# Sheet1.net
KiCad netlist of a schematic drawn in Altium Designer
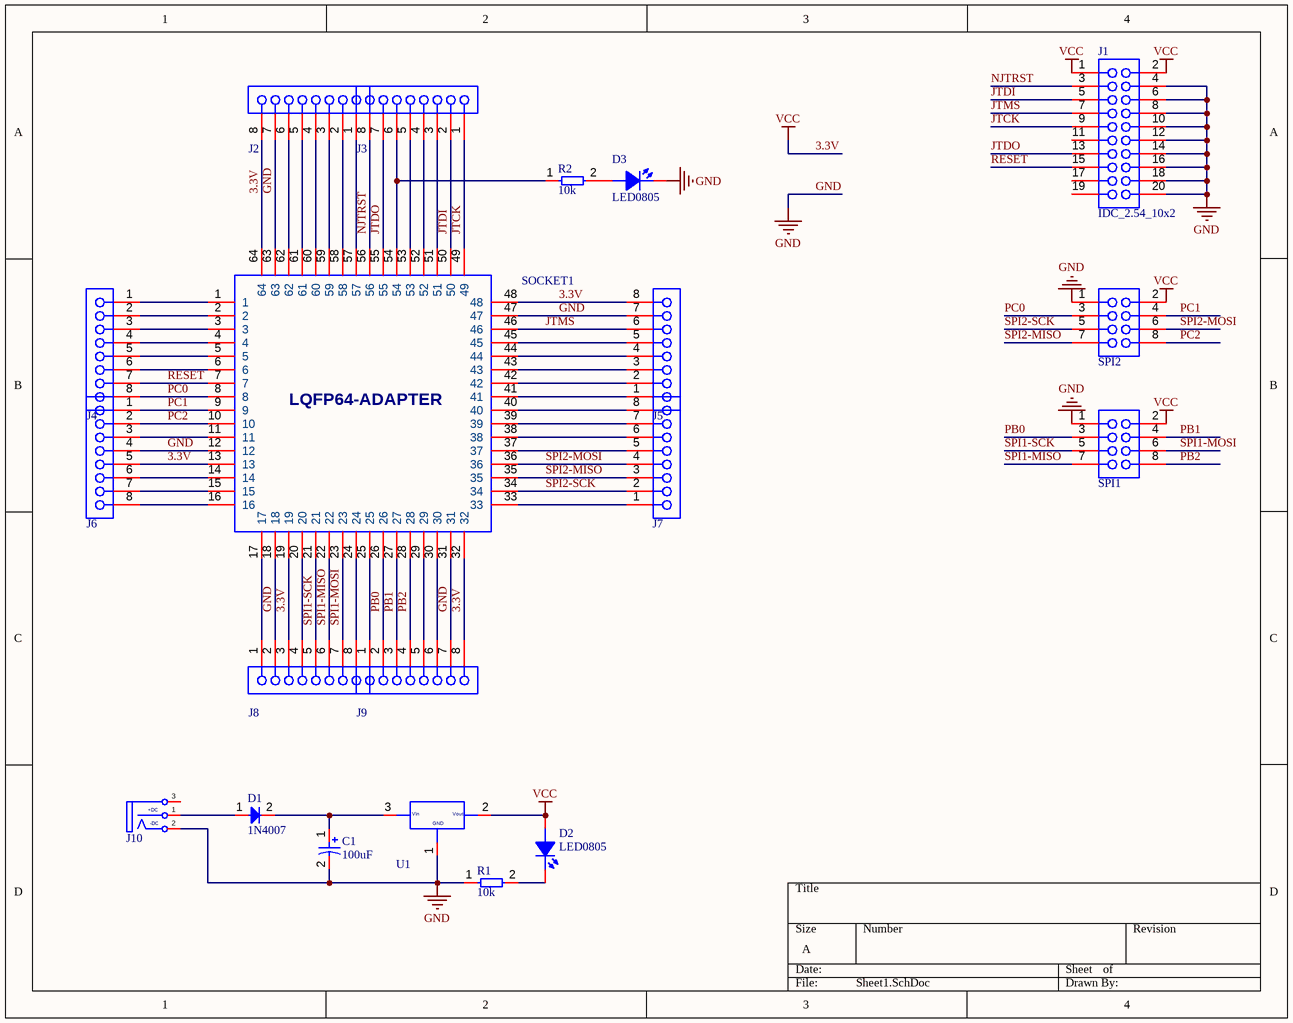
[diagram p0: Sheet1.SchDoc]

(export (version "E")
  (design (tool "Eeschema 10.0.6"))
  (components
    (comp (ref "C1")
      (value "100uF")
      (footprint "CAP_RAD_7mm")
      (libsource (lib "SMDLibrary") (part "Capacitor(Radian)"))
    )
    (comp (ref "D1") (value "1N4007") (footprint "DO-41") (libsource (lib "SMDLibrary") (part "1N4007")))
    (comp (ref "D2") (value "LED0805") (footprint "L0805RED") (libsource (lib "SMDLibrary") (part "LED0805")))
    (comp (ref "D3") (value "LED0805") (footprint "L0805RED") (libsource (lib "SMDLibrary") (part "LED0805")))
    (comp (ref "J1")
      (value "IDC_2.54_10x2")
      (footprint "IDC_CONNECTOR_20_2.54")
      (libsource (lib "SMDLibrary") (part "IDC_2.54_10x2"))
    )
    (comp (ref "J2")
      (value "Header 8x1 TH Pitch 2.54mm")
      (footprint "Header 8x1 TH Pitch 2.54mm")
      (libsource (lib "") (part "Header 8x1 TH Pitch 2.54mm_3"))
    )
    (comp (ref "J3")
      (value "Header 8x1 TH Pitch 2.54mm")
      (footprint "Header 8x1 TH Pitch 2.54mm")
      (libsource (lib "") (part "Header 8x1 TH Pitch 2.54mm_3"))
    )
    (comp (ref "J4")
      (value "Header 8x1 TH Pitch 2.54mm")
      (footprint "Header 8x1 TH Pitch 2.54mm")
      (libsource (lib "") (part "Header 8x1 TH Pitch 2.54mm_2"))
    )
    (comp (ref "J5")
      (value "Header 8x1 TH Pitch 2.54mm")
      (footprint "Header 8x1 TH Pitch 2.54mm")
      (libsource (lib "") (part "Header 8x1 TH Pitch 2.54mm_1"))
    )
    (comp (ref "J6")
      (value "Header 8x1 TH Pitch 2.54mm")
      (footprint "Header 8x1 TH Pitch 2.54mm")
      (libsource (lib "") (part "Header 8x1 TH Pitch 2.54mm_2"))
    )
    (comp (ref "J7")
      (value "Header 8x1 TH Pitch 2.54mm")
      (footprint "Header 8x1 TH Pitch 2.54mm")
      (libsource (lib "") (part "Header 8x1 TH Pitch 2.54mm_1"))
    )
    (comp (ref "J8")
      (value "Header 8x1 TH Pitch 2.54mm")
      (footprint "Header 8x1 TH Pitch 2.54mm")
      (libsource (lib "SMDLibrary") (part "Header 8x1 TH Pitch 2.54mm"))
    )
    (comp (ref "J9")
      (value "Header 8x1 TH Pitch 2.54mm")
      (footprint "Header 8x1 TH Pitch 2.54mm")
      (libsource (lib "SMDLibrary") (part "Header 8x1 TH Pitch 2.54mm"))
    )
    (comp (ref "J10")
      (value "Connector")
      (footprint "DC_K375A_Power")
      (libsource (lib "SMDLibrary") (part "JackDC"))
    )
    (comp (ref "R1") (value "10k") (footprint "R0805") (libsource (lib "SMDLibrary") (part "Resistor SMD")))
    (comp (ref "R2") (value "10k") (footprint "R0805") (libsource (lib "SMDLibrary") (part "Resistor SMD")))
    (comp (ref "SOCKET1")
      (value "SOCKET-ADAPTER-OTQ-64-05-03")
      (footprint "SOCKET-ADAPTER-OTQ-64-05-03")
      (libsource (lib "SMDLibrary") (part "SOCKET-ADAPTER-OTQ-64-05-03"))
    )
    (comp (ref "SPI1")
      (value "Header 4x2 TH Pitch 2.54mm")
      (footprint "Header 4x2 TH Pitch 2.54mm")
      (libsource (lib "SMDLibrary") (part "Header 4x2 TH Pitch 2.54mm"))
    )
    (comp (ref "SPI2")
      (value "Header 4x2 TH Pitch 2.54mm")
      (footprint "Header 4x2 TH Pitch 2.54mm")
      (libsource (lib "SMDLibrary") (part "Header 4x2 TH Pitch 2.54mm"))
    )
    (comp (ref "U1")
      (value "AMS1117")
      (footprint "SOT223-3")
      (libsource (lib "SMDLibrary") (part "AMS1117(SOT-223)"))
    )
  )
  (nets
    (net (code "1") (name "/JTCK") (class "Default")
      (node (ref "J1") (pin "9") (pinfunction "9_9") (pintype "passive"))
      (node (ref "J3") (pin "1") (pinfunction "1_1") (pintype "passive"))
      (node (ref "SOCKET1") (pin "49") (pinfunction "49_49") (pintype "passive"))
    )
    (net (code "2") (name "/JTDI") (class "Default")
      (node (ref "J1") (pin "5") (pinfunction "5_5") (pintype "passive"))
      (node (ref "J3") (pin "2") (pinfunction "2_2") (pintype "passive"))
      (node (ref "SOCKET1") (pin "50") (pinfunction "50_50") (pintype "passive"))
    )
    (net (code "3") (name "/JTDO") (class "Default")
      (node (ref "J1") (pin "13") (pinfunction "13_13") (pintype "passive"))
      (node (ref "J3") (pin "7") (pinfunction "7_7") (pintype "passive"))
      (node (ref "SOCKET1") (pin "55") (pinfunction "55_55") (pintype "passive"))
    )
    (net (code "4") (name "/JTMS") (class "Default")
      (node (ref "J1") (pin "7") (pinfunction "7_7") (pintype "passive"))
      (node (ref "J5") (pin "6") (pinfunction "6_6") (pintype "passive"))
      (node (ref "SOCKET1") (pin "46") (pinfunction "46_46") (pintype "passive"))
    )
    (net (code "5") (name "/NJTRST") (class "Default")
      (node (ref "J1") (pin "3") (pinfunction "3_3") (pintype "passive"))
      (node (ref "J3") (pin "8") (pinfunction "8_8") (pintype "passive"))
      (node (ref "SOCKET1") (pin "56") (pinfunction "56_56") (pintype "passive"))
    )
    (net (code "6") (name "/PB0") (class "Default")
      (node (ref "J9") (pin "2") (pinfunction "2_2") (pintype "passive"))
      (node (ref "SOCKET1") (pin "26") (pinfunction "26_26") (pintype "passive"))
      (node (ref "SPI1") (pin "3") (pinfunction "3_3") (pintype "passive"))
    )
    (net (code "7") (name "/PB1") (class "Default")
      (node (ref "J9") (pin "3") (pinfunction "3_3") (pintype "passive"))
      (node (ref "SOCKET1") (pin "27") (pinfunction "27_27") (pintype "passive"))
      (node (ref "SPI1") (pin "4") (pinfunction "4_4") (pintype "passive"))
    )
    (net (code "8") (name "/PB2") (class "Default")
      (node (ref "J9") (pin "4") (pinfunction "4_4") (pintype "passive"))
      (node (ref "SOCKET1") (pin "28") (pinfunction "28_28") (pintype "passive"))
      (node (ref "SPI1") (pin "8") (pinfunction "8_8") (pintype "passive"))
    )
    (net (code "9") (name "/PC0") (class "Default")
      (node (ref "J4") (pin "8") (pinfunction "8_8") (pintype "passive"))
      (node (ref "SOCKET1") (pin "8") (pinfunction "8_8") (pintype "passive"))
      (node (ref "SPI2") (pin "3") (pinfunction "3_3") (pintype "passive"))
    )
    (net (code "10") (name "/PC1") (class "Default")
      (node (ref "J6") (pin "1") (pinfunction "1_1") (pintype "passive"))
      (node (ref "SOCKET1") (pin "9") (pinfunction "9_9") (pintype "passive"))
      (node (ref "SPI2") (pin "4") (pinfunction "4_4") (pintype "passive"))
    )
    (net (code "11") (name "/PC2") (class "Default")
      (node (ref "J6") (pin "2") (pinfunction "2_2") (pintype "passive"))
      (node (ref "SOCKET1") (pin "10") (pinfunction "10_10") (pintype "passive"))
      (node (ref "SPI2") (pin "8") (pinfunction "8_8") (pintype "passive"))
    )
    (net (code "12") (name "/RESET") (class "Default")
      (node (ref "J1") (pin "15") (pinfunction "15_15") (pintype "passive"))
      (node (ref "J4") (pin "7") (pinfunction "7_7") (pintype "passive"))
      (node (ref "SOCKET1") (pin "7") (pinfunction "7_7") (pintype "passive"))
    )
    (net (code "13") (name "/SPI1-MISO") (class "Default")
      (node (ref "J8") (pin "6") (pinfunction "6_6") (pintype "passive"))
      (node (ref "SOCKET1") (pin "22") (pinfunction "22_22") (pintype "passive"))
      (node (ref "SPI1") (pin "7") (pinfunction "7_7") (pintype "passive"))
    )
    (net (code "14") (name "/SPI1-MOSI") (class "Default")
      (node (ref "J8") (pin "7") (pinfunction "7_7") (pintype "passive"))
      (node (ref "SOCKET1") (pin "23") (pinfunction "23_23") (pintype "passive"))
      (node (ref "SPI1") (pin "6") (pinfunction "6_6") (pintype "passive"))
    )
    (net (code "15") (name "/SPI1-SCK") (class "Default")
      (node (ref "J8") (pin "5") (pinfunction "5_5") (pintype "passive"))
      (node (ref "SOCKET1") (pin "21") (pinfunction "21_21") (pintype "passive"))
      (node (ref "SPI1") (pin "5") (pinfunction "5_5") (pintype "passive"))
    )
    (net (code "16") (name "/SPI2-MISO") (class "Default")
      (node (ref "J7") (pin "3") (pinfunction "3_3") (pintype "passive"))
      (node (ref "SOCKET1") (pin "35") (pinfunction "35_35") (pintype "passive"))
      (node (ref "SPI2") (pin "7") (pinfunction "7_7") (pintype "passive"))
    )
    (net (code "17") (name "/SPI2-MOSI") (class "Default")
      (node (ref "J7") (pin "4") (pinfunction "4_4") (pintype "passive"))
      (node (ref "SOCKET1") (pin "36") (pinfunction "36_36") (pintype "passive"))
      (node (ref "SPI2") (pin "6") (pinfunction "6_6") (pintype "passive"))
    )
    (net (code "18") (name "/SPI2-SCK") (class "Default")
      (node (ref "J7") (pin "2") (pinfunction "2_2") (pintype "passive"))
      (node (ref "SOCKET1") (pin "34") (pinfunction "34_34") (pintype "passive"))
      (node (ref "SPI2") (pin "5") (pinfunction "5_5") (pintype "passive"))
    )
    (net (code "19") (name "GND") (class "Default")
      (node (ref "C1") (pin "2") (pinfunction "2_2") (pintype "passive"))
      (node (ref "D3") (pin "2") (pinfunction "K_2") (pintype "passive"))
      (node (ref "J1") (pin "10") (pinfunction "10_10") (pintype "passive"))
      (node (ref "J1") (pin "12") (pinfunction "12_12") (pintype "passive"))
      (node (ref "J1") (pin "14") (pinfunction "14_14") (pintype "passive"))
      (node (ref "J1") (pin "16") (pinfunction "16_16") (pintype "passive"))
      (node (ref "J1") (pin "18") (pinfunction "18_18") (pintype "passive"))
      (node (ref "J1") (pin "20") (pinfunction "20_20") (pintype "passive"))
      (node (ref "J1") (pin "4") (pinfunction "4_4") (pintype "passive"))
      (node (ref "J1") (pin "6") (pinfunction "6_6") (pintype "passive"))
      (node (ref "J1") (pin "8") (pinfunction "8_8") (pintype "passive"))
      (node (ref "J10") (pin "2") (pinfunction "DC-_2") (pintype "passive"))
      (node (ref "J2") (pin "7") (pinfunction "7_7") (pintype "passive"))
      (node (ref "J5") (pin "7") (pinfunction "7_7") (pintype "passive"))
      (node (ref "J6") (pin "4") (pinfunction "4_4") (pintype "passive"))
      (node (ref "J8") (pin "2") (pinfunction "2_2") (pintype "passive"))
      (node (ref "J9") (pin "7") (pinfunction "7_7") (pintype "passive"))
      (node (ref "R1") (pin "1") (pinfunction "1_1") (pintype "passive"))
      (node (ref "SOCKET1") (pin "12") (pinfunction "12_12") (pintype "passive"))
      (node (ref "SOCKET1") (pin "18") (pinfunction "18_18") (pintype "passive"))
      (node (ref "SOCKET1") (pin "31") (pinfunction "31_31") (pintype "passive"))
      (node (ref "SOCKET1") (pin "47") (pinfunction "47_47") (pintype "passive"))
      (node (ref "SOCKET1") (pin "63") (pinfunction "63_63") (pintype "passive"))
      (node (ref "SPI1") (pin "1") (pinfunction "1_1") (pintype "passive"))
      (node (ref "SPI2") (pin "1") (pinfunction "1_1") (pintype "passive"))
      (node (ref "U1") (pin "1") (pinfunction "1_1") (pintype "passive"))
    )
    (net (code "20") (name "Net-(C1-Pad1)") (class "Default")
      (node (ref "C1") (pin "1") (pinfunction "1_1") (pintype "passive"))
      (node (ref "D1") (pin "2") (pinfunction "2_2") (pintype "passive"))
      (node (ref "U1") (pin "3") (pinfunction "3_3") (pintype "passive"))
    )
    (net (code "21") (name "Net-(D2-K)") (class "Default")
      (node (ref "D2") (pin "2") (pinfunction "K_2") (pintype "passive"))
      (node (ref "R1") (pin "2") (pinfunction "2_2") (pintype "passive"))
    )
    (net (code "22") (name "Net-(D3-A)") (class "Default")
      (node (ref "D3") (pin "1") (pinfunction "A_1") (pintype "passive"))
      (node (ref "R2") (pin "2") (pinfunction "2_2") (pintype "passive"))
    )
    (net (code "23") (name "Net-(J2-Pad1)") (class "Default")
      (node (ref "J2") (pin "1") (pinfunction "1_1") (pintype "passive"))
      (node (ref "SOCKET1") (pin "57") (pinfunction "57_57") (pintype "passive"))
    )
    (net (code "24") (name "Net-(J2-Pad2)") (class "Default")
      (node (ref "J2") (pin "2") (pinfunction "2_2") (pintype "passive"))
      (node (ref "SOCKET1") (pin "58") (pinfunction "58_58") (pintype "passive"))
    )
    (net (code "25") (name "Net-(J2-Pad3)") (class "Default")
      (node (ref "J2") (pin "3") (pinfunction "3_3") (pintype "passive"))
      (node (ref "SOCKET1") (pin "59") (pinfunction "59_59") (pintype "passive"))
    )
    (net (code "26") (name "Net-(J2-Pad4)") (class "Default")
      (node (ref "J2") (pin "4") (pinfunction "4_4") (pintype "passive"))
      (node (ref "SOCKET1") (pin "60") (pinfunction "60_60") (pintype "passive"))
    )
    (net (code "27") (name "Net-(J2-Pad5)") (class "Default")
      (node (ref "J2") (pin "5") (pinfunction "5_5") (pintype "passive"))
      (node (ref "SOCKET1") (pin "61") (pinfunction "61_61") (pintype "passive"))
    )
    (net (code "28") (name "Net-(J2-Pad6)") (class "Default")
      (node (ref "J2") (pin "6") (pinfunction "6_6") (pintype "passive"))
      (node (ref "SOCKET1") (pin "62") (pinfunction "62_62") (pintype "passive"))
    )
    (net (code "29") (name "Net-(J3-Pad3)") (class "Default")
      (node (ref "J3") (pin "3") (pinfunction "3_3") (pintype "passive"))
      (node (ref "SOCKET1") (pin "51") (pinfunction "51_51") (pintype "passive"))
    )
    (net (code "30") (name "Net-(J3-Pad4)") (class "Default")
      (node (ref "J3") (pin "4") (pinfunction "4_4") (pintype "passive"))
      (node (ref "SOCKET1") (pin "52") (pinfunction "52_52") (pintype "passive"))
    )
    (net (code "31") (name "Net-(J3-Pad5)") (class "Default")
      (node (ref "J3") (pin "5") (pinfunction "5_5") (pintype "passive"))
      (node (ref "SOCKET1") (pin "53") (pinfunction "53_53") (pintype "passive"))
    )
    (net (code "32") (name "Net-(J3-Pad6)") (class "Default")
      (node (ref "J3") (pin "6") (pinfunction "6_6") (pintype "passive"))
      (node (ref "R2") (pin "1") (pinfunction "1_1") (pintype "passive"))
      (node (ref "SOCKET1") (pin "54") (pinfunction "54_54") (pintype "passive"))
    )
    (net (code "33") (name "Net-(J4-Pad1)") (class "Default")
      (node (ref "J4") (pin "1") (pinfunction "1_1") (pintype "passive"))
      (node (ref "SOCKET1") (pin "1") (pinfunction "1_1") (pintype "passive"))
    )
    (net (code "34") (name "Net-(J4-Pad2)") (class "Default")
      (node (ref "J4") (pin "2") (pinfunction "2_2") (pintype "passive"))
      (node (ref "SOCKET1") (pin "2") (pinfunction "2_2") (pintype "passive"))
    )
    (net (code "35") (name "Net-(J4-Pad3)") (class "Default")
      (node (ref "J4") (pin "3") (pinfunction "3_3") (pintype "passive"))
      (node (ref "SOCKET1") (pin "3") (pinfunction "3_3") (pintype "passive"))
    )
    (net (code "36") (name "Net-(J4-Pad4)") (class "Default")
      (node (ref "J4") (pin "4") (pinfunction "4_4") (pintype "passive"))
      (node (ref "SOCKET1") (pin "4") (pinfunction "4_4") (pintype "passive"))
    )
    (net (code "37") (name "Net-(J4-Pad5)") (class "Default")
      (node (ref "J4") (pin "5") (pinfunction "5_5") (pintype "passive"))
      (node (ref "SOCKET1") (pin "5") (pinfunction "5_5") (pintype "passive"))
    )
    (net (code "38") (name "Net-(J4-Pad6)") (class "Default")
      (node (ref "J4") (pin "6") (pinfunction "6_6") (pintype "passive"))
      (node (ref "SOCKET1") (pin "6") (pinfunction "6_6") (pintype "passive"))
    )
    (net (code "39") (name "Net-(J5-Pad1)") (class "Default")
      (node (ref "J5") (pin "1") (pinfunction "1_1") (pintype "passive"))
      (node (ref "SOCKET1") (pin "41") (pinfunction "41_41") (pintype "passive"))
    )
    (net (code "40") (name "Net-(J5-Pad2)") (class "Default")
      (node (ref "J5") (pin "2") (pinfunction "2_2") (pintype "passive"))
      (node (ref "SOCKET1") (pin "42") (pinfunction "42_42") (pintype "passive"))
    )
    (net (code "41") (name "Net-(J5-Pad3)") (class "Default")
      (node (ref "J5") (pin "3") (pinfunction "3_3") (pintype "passive"))
      (node (ref "SOCKET1") (pin "43") (pinfunction "43_43") (pintype "passive"))
    )
    (net (code "42") (name "Net-(J5-Pad4)") (class "Default")
      (node (ref "J5") (pin "4") (pinfunction "4_4") (pintype "passive"))
      (node (ref "SOCKET1") (pin "44") (pinfunction "44_44") (pintype "passive"))
    )
    (net (code "43") (name "Net-(J5-Pad5)") (class "Default")
      (node (ref "J5") (pin "5") (pinfunction "5_5") (pintype "passive"))
      (node (ref "SOCKET1") (pin "45") (pinfunction "45_45") (pintype "passive"))
    )
    (net (code "44") (name "Net-(J6-Pad3)") (class "Default")
      (node (ref "J6") (pin "3") (pinfunction "3_3") (pintype "passive"))
      (node (ref "SOCKET1") (pin "11") (pinfunction "11_11") (pintype "passive"))
    )
    (net (code "45") (name "Net-(J6-Pad6)") (class "Default")
      (node (ref "J6") (pin "6") (pinfunction "6_6") (pintype "passive"))
      (node (ref "SOCKET1") (pin "14") (pinfunction "14_14") (pintype "passive"))
    )
    (net (code "46") (name "Net-(J6-Pad7)") (class "Default")
      (node (ref "J6") (pin "7") (pinfunction "7_7") (pintype "passive"))
      (node (ref "SOCKET1") (pin "15") (pinfunction "15_15") (pintype "passive"))
    )
    (net (code "47") (name "Net-(J6-Pad8)") (class "Default")
      (node (ref "J6") (pin "8") (pinfunction "8_8") (pintype "passive"))
      (node (ref "SOCKET1") (pin "16") (pinfunction "16_16") (pintype "passive"))
    )
    (net (code "48") (name "Net-(J7-Pad1)") (class "Default")
      (node (ref "J7") (pin "1") (pinfunction "1_1") (pintype "passive"))
      (node (ref "SOCKET1") (pin "33") (pinfunction "33_33") (pintype "passive"))
    )
    (net (code "49") (name "Net-(J7-Pad5)") (class "Default")
      (node (ref "J7") (pin "5") (pinfunction "5_5") (pintype "passive"))
      (node (ref "SOCKET1") (pin "37") (pinfunction "37_37") (pintype "passive"))
    )
    (net (code "50") (name "Net-(J7-Pad6)") (class "Default")
      (node (ref "J7") (pin "6") (pinfunction "6_6") (pintype "passive"))
      (node (ref "SOCKET1") (pin "38") (pinfunction "38_38") (pintype "passive"))
    )
    (net (code "51") (name "Net-(J7-Pad7)") (class "Default")
      (node (ref "J7") (pin "7") (pinfunction "7_7") (pintype "passive"))
      (node (ref "SOCKET1") (pin "39") (pinfunction "39_39") (pintype "passive"))
    )
    (net (code "52") (name "Net-(J7-Pad8)") (class "Default")
      (node (ref "J7") (pin "8") (pinfunction "8_8") (pintype "passive"))
      (node (ref "SOCKET1") (pin "40") (pinfunction "40_40") (pintype "passive"))
    )
    (net (code "53") (name "Net-(J8-Pad1)") (class "Default")
      (node (ref "J8") (pin "1") (pinfunction "1_1") (pintype "passive"))
      (node (ref "SOCKET1") (pin "17") (pinfunction "17_17") (pintype "passive"))
    )
    (net (code "54") (name "Net-(J8-Pad4)") (class "Default")
      (node (ref "J8") (pin "4") (pinfunction "4_4") (pintype "passive"))
      (node (ref "SOCKET1") (pin "20") (pinfunction "20_20") (pintype "passive"))
    )
    (net (code "55") (name "Net-(J8-Pad8)") (class "Default")
      (node (ref "J8") (pin "8") (pinfunction "8_8") (pintype "passive"))
      (node (ref "SOCKET1") (pin "24") (pinfunction "24_24") (pintype "passive"))
    )
    (net (code "56") (name "Net-(J9-Pad1)") (class "Default")
      (node (ref "J9") (pin "1") (pinfunction "1_1") (pintype "passive"))
      (node (ref "SOCKET1") (pin "25") (pinfunction "25_25") (pintype "passive"))
    )
    (net (code "57") (name "Net-(J9-Pad5)") (class "Default")
      (node (ref "J9") (pin "5") (pinfunction "5_5") (pintype "passive"))
      (node (ref "SOCKET1") (pin "29") (pinfunction "29_29") (pintype "passive"))
    )
    (net (code "58") (name "Net-(J9-Pad6)") (class "Default")
      (node (ref "J9") (pin "6") (pinfunction "6_6") (pintype "passive"))
      (node (ref "SOCKET1") (pin "30") (pinfunction "30_30") (pintype "passive"))
    )
    (net (code "59") (name "Net-(J10-DS+)") (class "Default")
      (node (ref "D1") (pin "1") (pinfunction "1_1") (pintype "passive"))
      (node (ref "J10") (pin "1") (pinfunction "DS+_1") (pintype "power_in"))
    )
    (net (code "60") (name "VCC") (class "Default")
      (node (ref "D2") (pin "1") (pinfunction "A_1") (pintype "passive"))
      (node (ref "J1") (pin "1") (pinfunction "1_1") (pintype "passive"))
      (node (ref "J1") (pin "2") (pinfunction "2_2") (pintype "passive"))
      (node (ref "J2") (pin "8") (pinfunction "8_8") (pintype "passive"))
      (node (ref "J5") (pin "8") (pinfunction "8_8") (pintype "passive"))
      (node (ref "J6") (pin "5") (pinfunction "5_5") (pintype "passive"))
      (node (ref "J8") (pin "3") (pinfunction "3_3") (pintype "passive"))
      (node (ref "J9") (pin "8") (pinfunction "8_8") (pintype "passive"))
      (node (ref "SOCKET1") (pin "13") (pinfunction "13_13") (pintype "passive"))
      (node (ref "SOCKET1") (pin "19") (pinfunction "19_19") (pintype "passive"))
      (node (ref "SOCKET1") (pin "32") (pinfunction "32_32") (pintype "passive"))
      (node (ref "SOCKET1") (pin "48") (pinfunction "48_48") (pintype "passive"))
      (node (ref "SOCKET1") (pin "64") (pinfunction "64_64") (pintype "passive"))
      (node (ref "SPI1") (pin "2") (pinfunction "2_2") (pintype "passive"))
      (node (ref "SPI2") (pin "2") (pinfunction "2_2") (pintype "passive"))
      (node (ref "U1") (pin "2") (pinfunction "2_2") (pintype "passive"))
    )
    (net (code "61") (name "unconnected-(J1-Pad11)") (class "Default")
      (node (ref "J1") (pin "11") (pinfunction "11_11") (pintype "passive"))
    )
    (net (code "62") (name "unconnected-(J1-Pad17)") (class "Default")
      (node (ref "J1") (pin "17") (pinfunction "17_17") (pintype "passive"))
    )
    (net (code "63") (name "unconnected-(J1-Pad19)") (class "Default")
      (node (ref "J1") (pin "19") (pinfunction "19_19") (pintype "passive"))
    )
    (net (code "64") (name "unconnected-(J10-T-Pad3)") (class "Default")
      (node (ref "J10") (pin "3") (pinfunction "T_3") (pintype "passive"))
    )
  )
)
